# Main.net
KiCad netlist of a schematic drawn in EAGLE
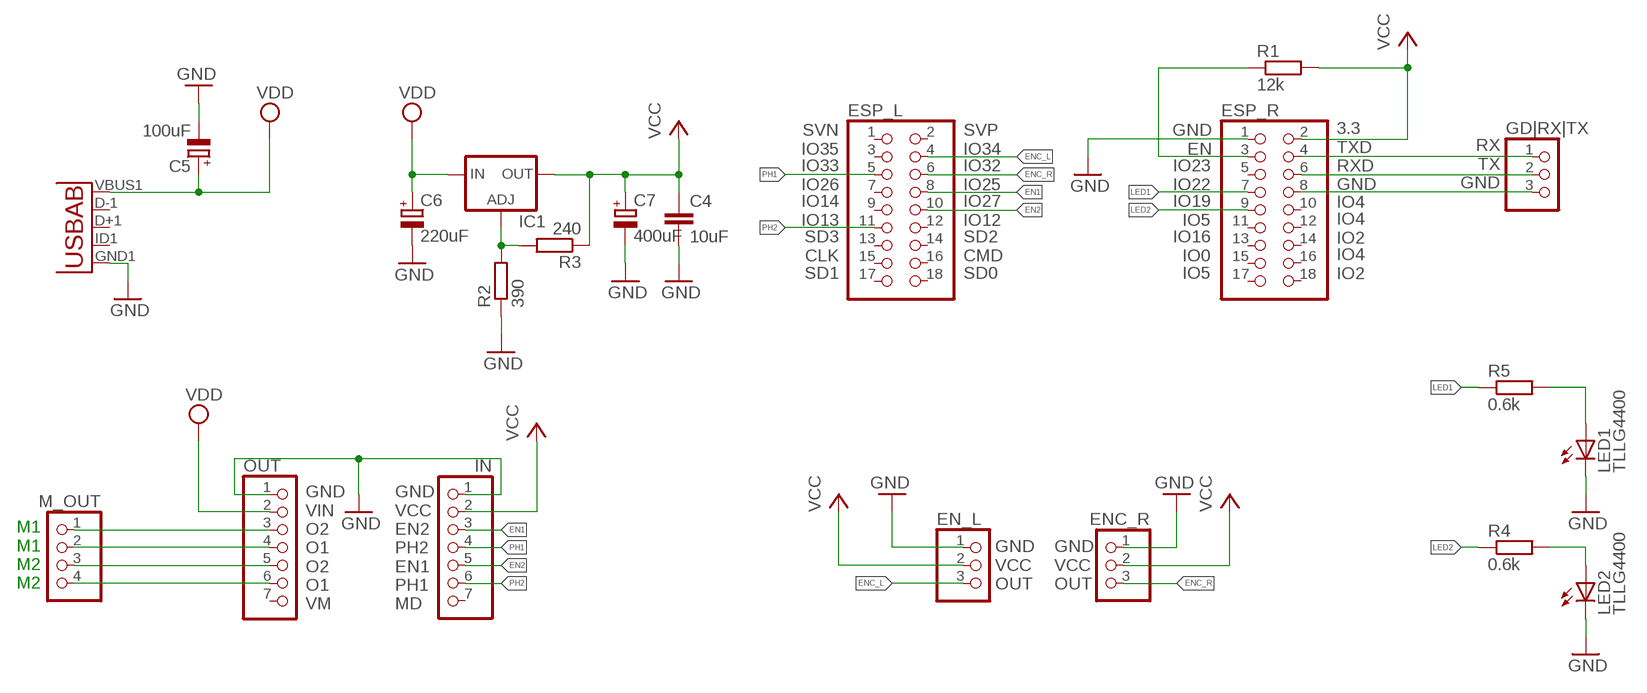
[diagram p0: schematic, sheet 1]

(export (version "E")
  (design (tool "Eeschema 10.0.6"))
  (components
    (comp (ref "C4")
      (value "10uF")
      (footprint "eagle-import:C050-025X075")
      (libsource (lib "eagle-import") (part "C-EU050-025X075"))
    )
    (comp (ref "C5")
      (value "100uF")
      (footprint "eagle-import:E2,5-6")
      (libsource (lib "eagle-import") (part "CPOL-EUE2.5-6"))
    )
    (comp (ref "C6")
      (value "220uF")
      (footprint "eagle-import:E2,5-6")
      (libsource (lib "eagle-import") (part "CPOL-EUE2.5-6"))
    )
    (comp (ref "C7")
      (value "400uF")
      (footprint "eagle-import:E2,5-6")
      (libsource (lib "eagle-import") (part "CPOL-EUE2.5-6"))
    )
    (comp (ref "ENC_R")
      (value "PINHD-1X3")
      (footprint "eagle-import:1X03")
      (libsource (lib "eagle-import") (part "PINHD-1X3"))
    )
    (comp (ref "EN_L")
      (value "PINHD-1X3")
      (footprint "eagle-import:1X03")
      (libsource (lib "eagle-import") (part "PINHD-1X3"))
    )
    (comp (ref "ESP_L")
      (value "PINHD-2X9")
      (footprint "eagle-import:2X09")
      (libsource (lib "eagle-import") (part "PINHD-2X9"))
    )
    (comp (ref "ESP_R")
      (value "PINHD-2X9")
      (footprint "eagle-import:2X09")
      (libsource (lib "eagle-import") (part "PINHD-2X9"))
    )
    (comp (ref "GD|RX|TX")
      (value "PINHD-1X3")
      (footprint "eagle-import:1X03")
      (libsource (lib "eagle-import") (part "PINHD-1X3"))
    )
    (comp (ref "IC1")
      (value "LM317TS")
      (footprint "eagle-import:317TS")
      (libsource (lib "eagle-import") (part "LM317TS"))
    )
    (comp (ref "IN")
      (value "PINHD-1X7")
      (footprint "eagle-import:1X07")
      (libsource (lib "eagle-import") (part "PINHD-1X7"))
    )
    (comp (ref "LED1")
      (value "TLLG4400")
      (footprint "eagle-import:LED3MM")
      (fields (field (name "MF") "VISHAY SEMICONDUCTOR"))
      (libsource (lib "eagle-import") (part "TLLG4400"))
    )
    (comp (ref "LED2")
      (value "TLLG4400")
      (footprint "eagle-import:LED3MM")
      (fields (field (name "MF") "VISHAY SEMICONDUCTOR"))
      (libsource (lib "eagle-import") (part "TLLG4400"))
    )
    (comp (ref "M_OUT")
      (value "PINHD-1X4")
      (footprint "eagle-import:1X04")
      (libsource (lib "eagle-import") (part "PINHD-1X4"))
    )
    (comp (ref "OUT")
      (value "PINHD-1X7")
      (footprint "eagle-import:1X07")
      (libsource (lib "eagle-import") (part "PINHD-1X7"))
    )
    (comp (ref "R1")
      (value "12k")
      (footprint "eagle-import:0207_10")
      (libsource (lib "eagle-import") (part "R-EU_0207/10"))
    )
    (comp (ref "R2")
      (value "390")
      (footprint "eagle-import:0207_10")
      (libsource (lib "eagle-import") (part "R-EU_0207/10"))
    )
    (comp (ref "R3")
      (value "240")
      (footprint "eagle-import:0207_10")
      (libsource (lib "eagle-import") (part "R-EU_0207/10"))
    )
    (comp (ref "R4")
      (value "0.6k")
      (footprint "eagle-import:0207_10")
      (libsource (lib "eagle-import") (part "R-EU_0207/10"))
    )
    (comp (ref "R5")
      (value "0.6k")
      (footprint "eagle-import:0207_10")
      (libsource (lib "eagle-import") (part "R-EU_0207/10"))
    )
    (comp (ref "U3")
      (value "USB\"\"")
      (footprint "eagle-import:USB-MICRO-SMD")
      (libsource (lib "eagle-import") (part "USB{dblquote}{dblquote}"))
    )
  )
  (nets
    (net (code "1") (name "EN1") (class "Default")
      (node (ref "ESP_L") (pin "8") (pinfunction "8_8") (pintype "passive"))
      (node (ref "IN") (pin "3") (pinfunction "3_3") (pintype "passive"))
    )
    (net (code "2") (name "EN2") (class "Default")
      (node (ref "ESP_L") (pin "10") (pinfunction "10_10") (pintype "passive"))
      (node (ref "IN") (pin "5") (pinfunction "5_5") (pintype "passive"))
    )
    (net (code "3") (name "ENC_L") (class "Default")
      (node (ref "EN_L") (pin "3") (pinfunction "3_3") (pintype "passive"))
      (node (ref "ESP_L") (pin "4") (pinfunction "4_4") (pintype "passive"))
    )
    (net (code "4") (name "ENC_R") (class "Default")
      (node (ref "ENC_R") (pin "3") (pinfunction "3_3") (pintype "passive"))
      (node (ref "ESP_L") (pin "6") (pinfunction "6_6") (pintype "passive"))
    )
    (net (code "5") (name "GND") (class "Default")
      (node (ref "C4") (pin "2") (pinfunction "2_2") (pintype "passive"))
      (node (ref "C5") (pin "-") (pinfunction "-_-") (pintype "passive"))
      (node (ref "C6") (pin "-") (pinfunction "-_-") (pintype "passive"))
      (node (ref "C7") (pin "-") (pinfunction "-_-") (pintype "passive"))
      (node (ref "ENC_R") (pin "1") (pinfunction "1_1") (pintype "passive"))
      (node (ref "EN_L") (pin "1") (pinfunction "1_1") (pintype "passive"))
      (node (ref "ESP_R") (pin "1") (pinfunction "1_1") (pintype "passive"))
      (node (ref "IN") (pin "1") (pinfunction "1_1") (pintype "passive"))
      (node (ref "LED1") (pin "K") (pinfunction "C_K") (pintype "passive"))
      (node (ref "LED2") (pin "K") (pinfunction "C_K") (pintype "passive"))
      (node (ref "OUT") (pin "1") (pinfunction "1_1") (pintype "passive"))
      (node (ref "R2") (pin "1") (pinfunction "1_1") (pintype "passive"))
      (node (ref "U3") (pin "GND1") (pinfunction "GND_GND1") (pintype "bidirectional"))
    )
    (net (code "6") (name "LED1") (class "Default")
      (node (ref "ESP_R") (pin "7") (pinfunction "7_7") (pintype "passive"))
      (node (ref "R5") (pin "1") (pinfunction "1_1") (pintype "passive"))
    )
    (net (code "7") (name "LED2") (class "Default")
      (node (ref "ESP_R") (pin "9") (pinfunction "9_9") (pintype "passive"))
      (node (ref "R4") (pin "1") (pinfunction "1_1") (pintype "passive"))
    )
    (net (code "8") (name "Net-(ESP_R-Pad3)") (class "Default")
      (node (ref "ESP_R") (pin "3") (pinfunction "3_3") (pintype "passive"))
      (node (ref "R1") (pin "1") (pinfunction "1_1") (pintype "passive"))
    )
    (net (code "9") (name "Net-(ESP_R-Pad4)") (class "Default")
      (node (ref "ESP_R") (pin "4") (pinfunction "4_4") (pintype "passive"))
      (node (ref "GD|RX|TX") (pin "1") (pinfunction "1_1") (pintype "passive"))
    )
    (net (code "10") (name "Net-(ESP_R-Pad6)") (class "Default")
      (node (ref "ESP_R") (pin "6") (pinfunction "6_6") (pintype "passive"))
      (node (ref "GD|RX|TX") (pin "2") (pinfunction "2_2") (pintype "passive"))
    )
    (net (code "11") (name "Net-(ESP_R-Pad8)") (class "Default")
      (node (ref "ESP_R") (pin "8") (pinfunction "8_8") (pintype "passive"))
      (node (ref "GD|RX|TX") (pin "3") (pinfunction "3_3") (pintype "passive"))
    )
    (net (code "12") (name "Net-(IC1-ADJ)") (class "Default")
      (node (ref "IC1") (pin "1") (pinfunction "ADJ_1") (pintype "input"))
      (node (ref "R2") (pin "2") (pinfunction "2_2") (pintype "passive"))
      (node (ref "R3") (pin "2") (pinfunction "2_2") (pintype "passive"))
    )
    (net (code "13") (name "Net-(LED1-PadA)") (class "Default")
      (node (ref "LED1") (pin "A") (pinfunction "A_A") (pintype "passive"))
      (node (ref "R5") (pin "2") (pinfunction "2_2") (pintype "passive"))
    )
    (net (code "14") (name "Net-(LED2-PadA)") (class "Default")
      (node (ref "LED2") (pin "A") (pinfunction "A_A") (pintype "passive"))
      (node (ref "R4") (pin "2") (pinfunction "2_2") (pintype "passive"))
    )
    (net (code "15") (name "Net-(M_OUT-Pad1)") (class "Default")
      (node (ref "M_OUT") (pin "1") (pinfunction "1_1") (pintype "passive"))
      (node (ref "OUT") (pin "3") (pinfunction "3_3") (pintype "passive"))
    )
    (net (code "16") (name "Net-(M_OUT-Pad2)") (class "Default")
      (node (ref "M_OUT") (pin "2") (pinfunction "2_2") (pintype "passive"))
      (node (ref "OUT") (pin "4") (pinfunction "4_4") (pintype "passive"))
    )
    (net (code "17") (name "Net-(M_OUT-Pad3)") (class "Default")
      (node (ref "M_OUT") (pin "3") (pinfunction "3_3") (pintype "passive"))
      (node (ref "OUT") (pin "5") (pinfunction "5_5") (pintype "passive"))
    )
    (net (code "18") (name "Net-(M_OUT-Pad4)") (class "Default")
      (node (ref "M_OUT") (pin "4") (pinfunction "4_4") (pintype "passive"))
      (node (ref "OUT") (pin "6") (pinfunction "6_6") (pintype "passive"))
    )
    (net (code "19") (name "PH1") (class "Default")
      (node (ref "ESP_L") (pin "5") (pinfunction "5_5") (pintype "passive"))
      (node (ref "IN") (pin "4") (pinfunction "4_4") (pintype "passive"))
    )
    (net (code "20") (name "PH2") (class "Default")
      (node (ref "ESP_L") (pin "11") (pinfunction "11_11") (pintype "passive"))
      (node (ref "IN") (pin "6") (pinfunction "6_6") (pintype "passive"))
    )
    (net (code "21") (name "VCC") (class "Default")
      (node (ref "C4") (pin "1") (pinfunction "1_1") (pintype "passive"))
      (node (ref "C7") (pin "+") (pinfunction "+_+") (pintype "passive"))
      (node (ref "ENC_R") (pin "2") (pinfunction "2_2") (pintype "passive"))
      (node (ref "EN_L") (pin "2") (pinfunction "2_2") (pintype "passive"))
      (node (ref "ESP_R") (pin "2") (pinfunction "2_2") (pintype "passive"))
      (node (ref "IC1") (pin "2") (pinfunction "OUT_2") (pintype "passive"))
      (node (ref "IN") (pin "2") (pinfunction "2_2") (pintype "passive"))
      (node (ref "R1") (pin "2") (pinfunction "2_2") (pintype "passive"))
      (node (ref "R3") (pin "1") (pinfunction "1_1") (pintype "passive"))
    )
    (net (code "22") (name "VDD") (class "Default")
      (node (ref "C5") (pin "+") (pinfunction "+_+") (pintype "passive"))
      (node (ref "C6") (pin "+") (pinfunction "+_+") (pintype "passive"))
      (node (ref "IC1") (pin "3") (pinfunction "IN_3") (pintype "input"))
      (node (ref "OUT") (pin "2") (pinfunction "2_2") (pintype "passive"))
      (node (ref "U3") (pin "VBUS1") (pinfunction "VBUS_VBUS1") (pintype "bidirectional"))
    )
    (net (code "23") (name "unconnected-(ESP_L-Pad1)") (class "Default")
      (node (ref "ESP_L") (pin "1") (pinfunction "1_1") (pintype "passive"))
    )
    (net (code "24") (name "unconnected-(ESP_L-Pad2)") (class "Default")
      (node (ref "ESP_L") (pin "2") (pinfunction "2_2") (pintype "passive"))
    )
    (net (code "25") (name "unconnected-(ESP_L-Pad3)") (class "Default")
      (node (ref "ESP_L") (pin "3") (pinfunction "3_3") (pintype "passive"))
    )
    (net (code "26") (name "unconnected-(ESP_L-Pad7)") (class "Default")
      (node (ref "ESP_L") (pin "7") (pinfunction "7_7") (pintype "passive"))
    )
    (net (code "27") (name "unconnected-(ESP_L-Pad9)") (class "Default")
      (node (ref "ESP_L") (pin "9") (pinfunction "9_9") (pintype "passive"))
    )
    (net (code "28") (name "unconnected-(ESP_L-Pad12)") (class "Default")
      (node (ref "ESP_L") (pin "12") (pinfunction "12_12") (pintype "passive"))
    )
    (net (code "29") (name "unconnected-(ESP_L-Pad13)") (class "Default")
      (node (ref "ESP_L") (pin "13") (pinfunction "13_13") (pintype "passive"))
    )
    (net (code "30") (name "unconnected-(ESP_L-Pad14)") (class "Default")
      (node (ref "ESP_L") (pin "14") (pinfunction "14_14") (pintype "passive"))
    )
    (net (code "31") (name "unconnected-(ESP_L-Pad15)") (class "Default")
      (node (ref "ESP_L") (pin "15") (pinfunction "15_15") (pintype "passive"))
    )
    (net (code "32") (name "unconnected-(ESP_L-Pad16)") (class "Default")
      (node (ref "ESP_L") (pin "16") (pinfunction "16_16") (pintype "passive"))
    )
    (net (code "33") (name "unconnected-(ESP_L-Pad17)") (class "Default")
      (node (ref "ESP_L") (pin "17") (pinfunction "17_17") (pintype "passive"))
    )
    (net (code "34") (name "unconnected-(ESP_L-Pad18)") (class "Default")
      (node (ref "ESP_L") (pin "18") (pinfunction "18_18") (pintype "passive"))
    )
    (net (code "35") (name "unconnected-(ESP_R-Pad5)") (class "Default")
      (node (ref "ESP_R") (pin "5") (pinfunction "5_5") (pintype "passive"))
    )
    (net (code "36") (name "unconnected-(ESP_R-Pad10)") (class "Default")
      (node (ref "ESP_R") (pin "10") (pinfunction "10_10") (pintype "passive"))
    )
    (net (code "37") (name "unconnected-(ESP_R-Pad11)") (class "Default")
      (node (ref "ESP_R") (pin "11") (pinfunction "11_11") (pintype "passive"))
    )
    (net (code "38") (name "unconnected-(ESP_R-Pad12)") (class "Default")
      (node (ref "ESP_R") (pin "12") (pinfunction "12_12") (pintype "passive"))
    )
    (net (code "39") (name "unconnected-(ESP_R-Pad13)") (class "Default")
      (node (ref "ESP_R") (pin "13") (pinfunction "13_13") (pintype "passive"))
    )
    (net (code "40") (name "unconnected-(ESP_R-Pad14)") (class "Default")
      (node (ref "ESP_R") (pin "14") (pinfunction "14_14") (pintype "passive"))
    )
    (net (code "41") (name "unconnected-(ESP_R-Pad15)") (class "Default")
      (node (ref "ESP_R") (pin "15") (pinfunction "15_15") (pintype "passive"))
    )
    (net (code "42") (name "unconnected-(ESP_R-Pad16)") (class "Default")
      (node (ref "ESP_R") (pin "16") (pinfunction "16_16") (pintype "passive"))
    )
    (net (code "43") (name "unconnected-(ESP_R-Pad17)") (class "Default")
      (node (ref "ESP_R") (pin "17") (pinfunction "17_17") (pintype "passive"))
    )
    (net (code "44") (name "unconnected-(ESP_R-Pad18)") (class "Default")
      (node (ref "ESP_R") (pin "18") (pinfunction "18_18") (pintype "passive"))
    )
    (net (code "45") (name "unconnected-(IN-Pad7)") (class "Default")
      (node (ref "IN") (pin "7") (pinfunction "7_7") (pintype "passive"))
    )
    (net (code "46") (name "unconnected-(OUT-Pad7)") (class "Default")
      (node (ref "OUT") (pin "7") (pinfunction "7_7") (pintype "passive"))
    )
    (net (code "47") (name "unconnected-(U3-D+-PadD+1)") (class "Default")
      (node (ref "U3") (pin "D+1") (pinfunction "D+_D+1") (pintype "bidirectional"))
    )
    (net (code "48") (name "unconnected-(U3-D--PadD-1)") (class "Default")
      (node (ref "U3") (pin "D-1") (pinfunction "D-_D-1") (pintype "bidirectional"))
    )
    (net (code "49") (name "unconnected-(U3-USBID-PadID1)") (class "Default")
      (node (ref "U3") (pin "ID1") (pinfunction "USBID_ID1") (pintype "bidirectional"))
    )
  )
)
